# SolarPanel.net
KiCad netlist of a schematic drawn in Altium Designer
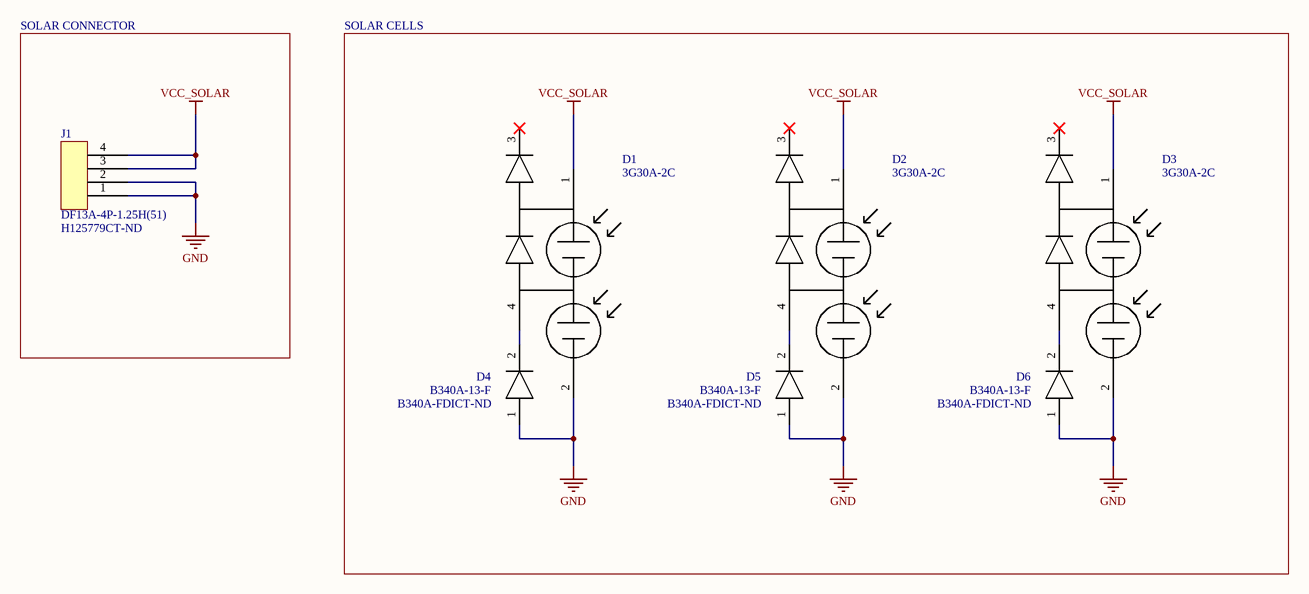
[diagram p0: SolarPanel.SchDoc]

(export (version "E")
  (design (tool "Eeschema 10.0.6"))
  (components
    (comp (ref "D1")
      (value "3G30A-2C")
      (footprint "3G30A_2C")
      (description "Solar cell x2")
      (libsource (lib "heron-general") (part "3G30A-2C"))
    )
    (comp (ref "D2")
      (value "3G30A-2C")
      (footprint "3G30A_2C")
      (description "Solar cell x2")
      (libsource (lib "heron-general") (part "3G30A-2C"))
    )
    (comp (ref "D3")
      (value "3G30A-2C")
      (footprint "3G30A_2C")
      (description "Solar cell x2")
      (libsource (lib "heron-general") (part "3G30A-2C"))
    )
    (comp (ref "D4")
      (value "B340A-13-F")
      (footprint "B340A-13-F")
      (description "Schottky diode")
      (fields (field (name "SUPPLIER PART NUMBER 1") "B340A-FDICT-ND"))
      (libsource (lib "heron-general") (part "B340A-13-F"))
    )
    (comp (ref "D5")
      (value "B340A-13-F")
      (footprint "B340A-13-F")
      (description "Schottky diode")
      (fields (field (name "SUPPLIER PART NUMBER 1") "B340A-FDICT-ND"))
      (libsource (lib "heron-general") (part "B340A-13-F"))
    )
    (comp (ref "D6")
      (value "B340A-13-F")
      (footprint "B340A-13-F")
      (description "Schottky diode")
      (fields (field (name "SUPPLIER PART NUMBER 1") "B340A-FDICT-ND"))
      (libsource (lib "heron-general") (part "B340A-13-F"))
    )
    (comp (ref "J1")
      (value "DF13A-4P-1.25H(51)")
      (footprint "DF13A-4P-1.25H(51)")
      (description "4 pos DF13 right angle surface mount connector")
      (fields (field (name "SUPPLIER PART NUMBER 1") "H125779CT-ND"))
      (libsource (lib "heron-general") (part "DF13A-4P-1.25H(51)"))
    )
  )
  (nets
    (net (code "1") (name "GND") (class "Default")
      (node (ref "D1") (pin "2") (pintype "passive"))
      (node (ref "D2") (pin "2") (pintype "passive"))
      (node (ref "D3") (pin "2") (pintype "passive"))
      (node (ref "D4") (pin "1") (pintype "passive"))
      (node (ref "D5") (pin "1") (pintype "passive"))
      (node (ref "D6") (pin "1") (pintype "passive"))
      (node (ref "J1") (pin "1") (pintype "passive"))
      (node (ref "J1") (pin "2") (pintype "passive"))
    )
    (net (code "2") (name "Net-(D1-Pad4)") (class "Default")
      (node (ref "D1") (pin "4") (pintype "passive"))
      (node (ref "D4") (pin "2") (pintype "passive"))
    )
    (net (code "3") (name "Net-(D2-Pad4)") (class "Default")
      (node (ref "D2") (pin "4") (pintype "passive"))
      (node (ref "D5") (pin "2") (pintype "passive"))
    )
    (net (code "4") (name "Net-(D3-Pad4)") (class "Default")
      (node (ref "D3") (pin "4") (pintype "passive"))
      (node (ref "D6") (pin "2") (pintype "passive"))
    )
    (net (code "5") (name "VCC_SOLAR") (class "Default")
      (node (ref "D1") (pin "1") (pintype "passive"))
      (node (ref "D2") (pin "1") (pintype "passive"))
      (node (ref "D3") (pin "1") (pintype "passive"))
      (node (ref "J1") (pin "3") (pintype "passive"))
      (node (ref "J1") (pin "4") (pintype "passive"))
    )
    (net (code "6") (name "unconnected-(D1-Pad3)") (class "Default")
      (node (ref "D1") (pin "3") (pintype "passive+no_connect"))
    )
    (net (code "7") (name "unconnected-(D2-Pad3)") (class "Default")
      (node (ref "D2") (pin "3") (pintype "passive+no_connect"))
    )
    (net (code "8") (name "unconnected-(D3-Pad3)") (class "Default")
      (node (ref "D3") (pin "3") (pintype "passive+no_connect"))
    )
  )
)
